# output2.net
KiCad netlist of a schematic drawn in EAGLE
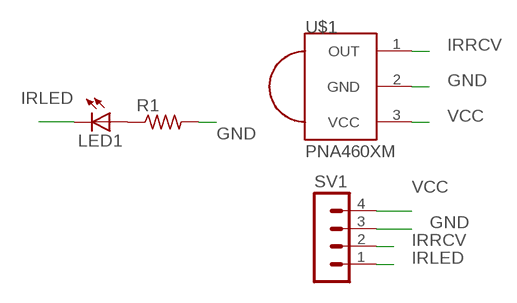
[diagram p0: schematic, sheet 1]

(export (version "E")
  (design (tool "Eeschema 10.0.6"))
  (components
    (comp (ref "LED1")
      (value "LED5MM")
      (footprint "eagle-import:LED5MM")
      (libsource (lib "eagle-import") (part "LED5MM"))
    )
    (comp (ref "R1")
      (value "RESISTOR1206")
      (footprint "eagle-import:1206")
      (libsource (lib "eagle-import") (part "RESISTOR1206"))
    )
    (comp (ref "SV1")
      (value "MA04-1")
      (footprint "eagle-import:MA04-1")
      (libsource (lib "eagle-import") (part "MA04-1"))
    )
    (comp (ref "U$1")
      (value "PNA460XM")
      (footprint "eagle-import:PNA460XM")
      (libsource (lib "eagle-import") (part "PNA460XM"))
    )
  )
  (nets
    (net (code "1") (name "/GND") (class "Default")
      (node (ref "R1") (pin "2") (pinfunction "2_2") (pintype "passive"))
      (node (ref "SV1") (pin "3") (pinfunction "3_3") (pintype "passive"))
      (node (ref "U$1") (pin "2") (pinfunction "GND_2") (pintype "power_in"))
    )
    (net (code "2") (name "/IRLED") (class "Default")
      (node (ref "LED1") (pin "K") (pinfunction "C_K") (pintype "passive"))
      (node (ref "SV1") (pin "1") (pinfunction "1_1") (pintype "passive"))
    )
    (net (code "3") (name "/IRRCV") (class "Default")
      (node (ref "SV1") (pin "2") (pinfunction "2_2") (pintype "passive"))
      (node (ref "U$1") (pin "1") (pinfunction "OUT_1") (pintype "output"))
    )
    (net (code "4") (name "/VCC") (class "Default")
      (node (ref "SV1") (pin "4") (pinfunction "4_4") (pintype "passive"))
      (node (ref "U$1") (pin "3") (pinfunction "VCC_3") (pintype "power_in"))
    )
    (net (code "5") (name "Net-(LED1-PadA)") (class "Default")
      (node (ref "LED1") (pin "A") (pinfunction "A_A") (pintype "passive"))
      (node (ref "R1") (pin "1") (pinfunction "1_1") (pintype "passive"))
    )
  )
)
